# LED_aluminum.net
KiCad netlist of a schematic drawn in Altium Designer
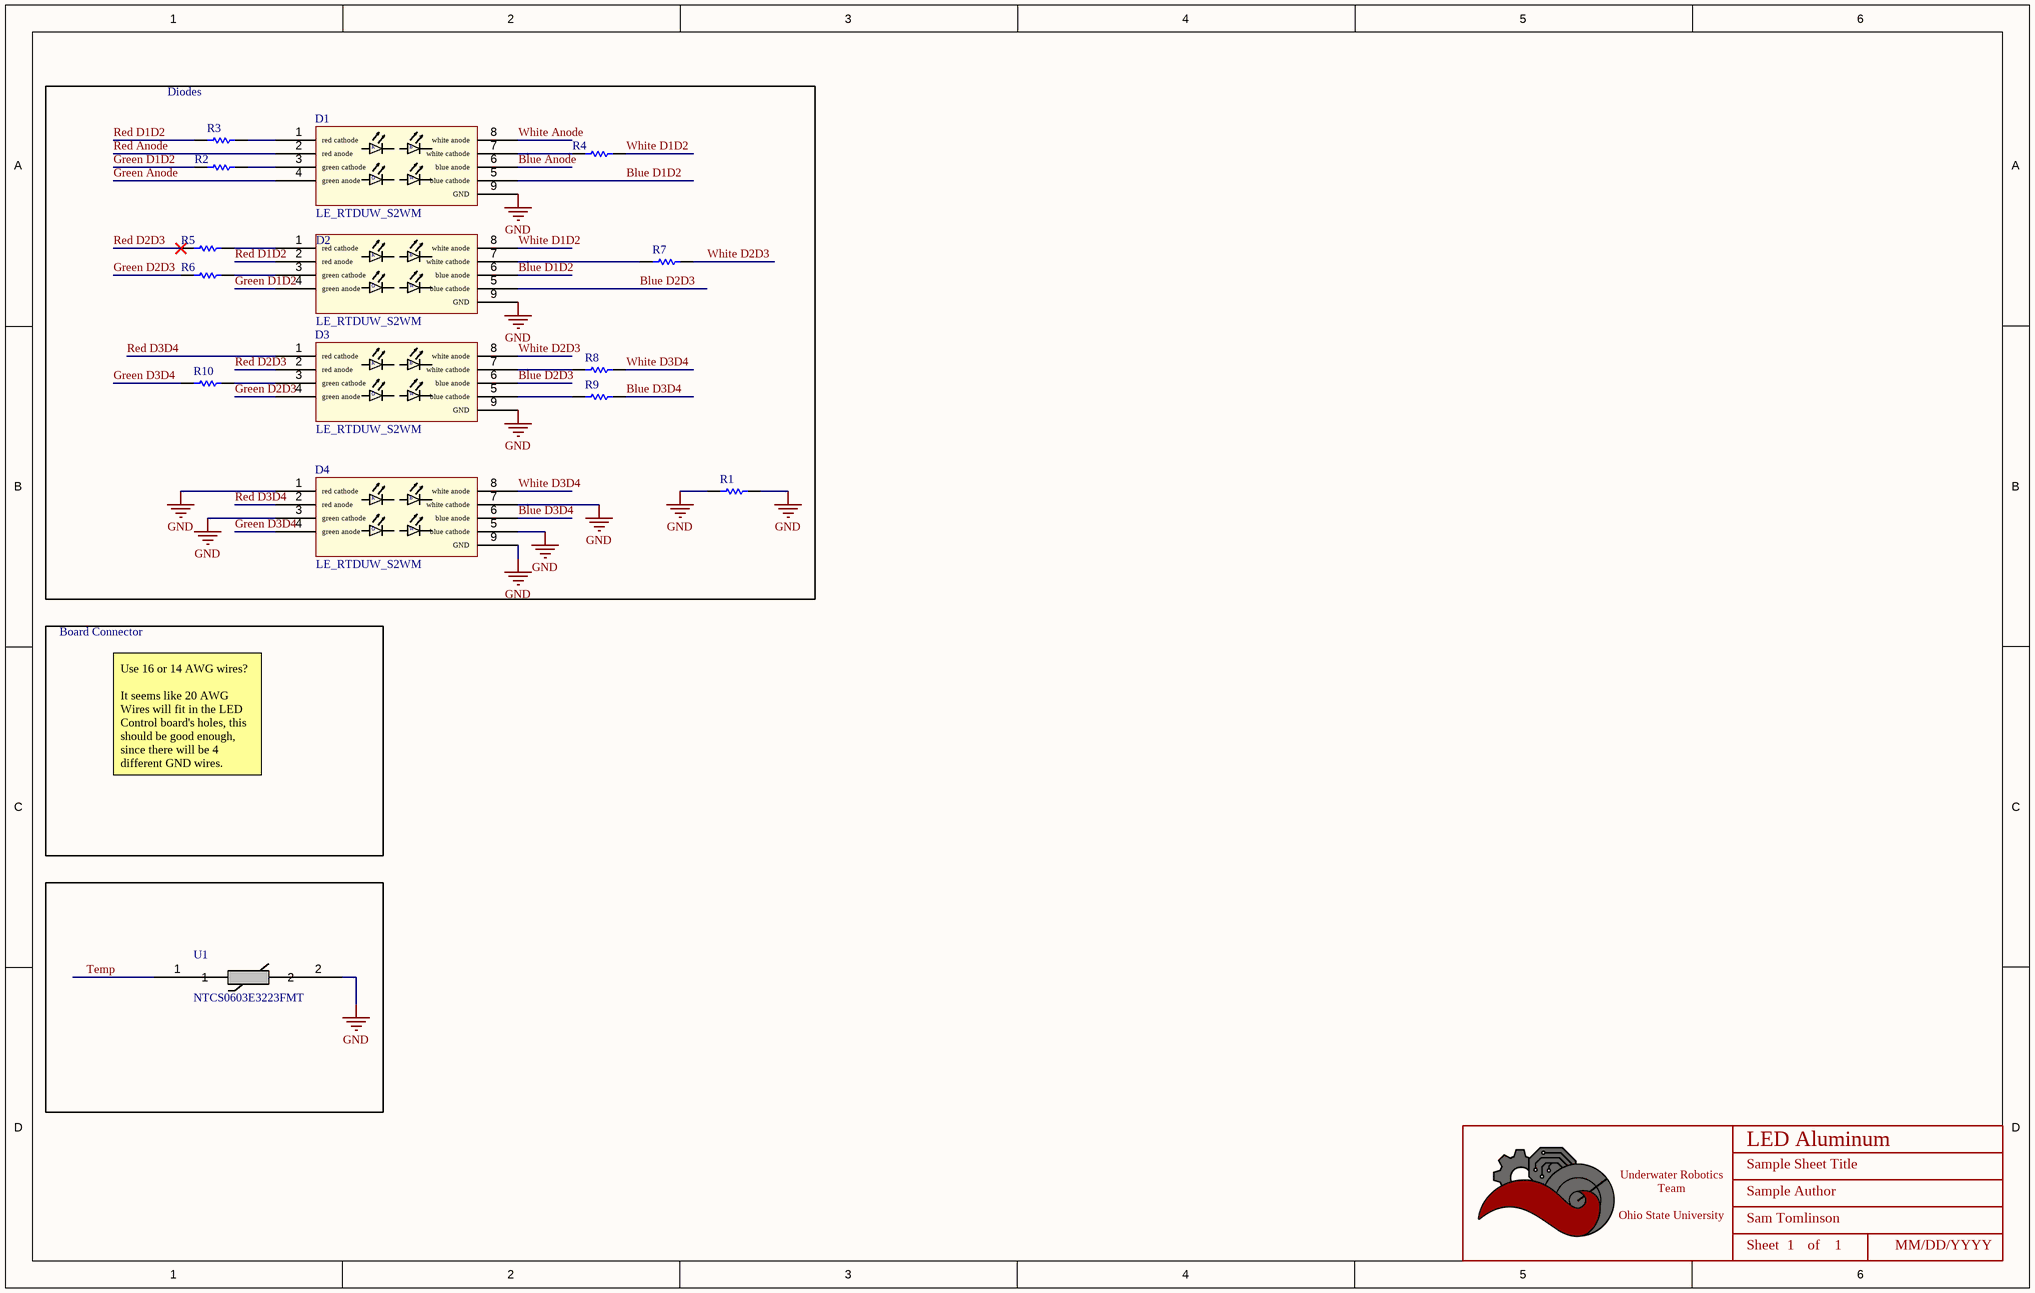
[diagram p0: LED_aluminum.SchDoc]

(export (version "E")
  (design (tool "Eeschema 10.0.6"))
  (components
    (comp (ref "*")
      (value "Title_Block")
      (footprint "LOGO")
      (description "UWRT Schematic Title Block Template\r\n\r\nCreated June 2021, Dylan Trainor")
      (libsource (lib "UWRT") (part "Title_Block"))
    )
    (comp (ref "D1")
      (value "LE_RTDUW_S2WM")
      (footprint "LE_RTDUW_S2WM")
      (description "LED OSTAR RGBW 625/527/453NM SMD")
      (libsource (lib "Diodes") (part "LE_RTDUW_S2WM"))
    )
    (comp (ref "D2")
      (value "LE_RTDUW_S2WM")
      (footprint "LE_RTDUW_S2WM")
      (description "LED OSTAR RGBW 625/527/453NM SMD")
      (libsource (lib "Diodes") (part "LE_RTDUW_S2WM"))
    )
    (comp (ref "D3")
      (value "LE_RTDUW_S2WM")
      (footprint "LE_RTDUW_S2WM")
      (description "LED OSTAR RGBW 625/527/453NM SMD")
      (libsource (lib "Diodes") (part "LE_RTDUW_S2WM"))
    )
    (comp (ref "D4")
      (value "LE_RTDUW_S2WM")
      (footprint "LE_RTDUW_S2WM")
      (description "LED OSTAR RGBW 625/527/453NM SMD")
      (libsource (lib "Diodes") (part "LE_RTDUW_S2WM"))
    )
    (comp (ref "R1")
      (value "Jumper 2512(6432)")
      (footprint "RESC2512(6432)_L")
      (description "Jumper 2512 (6432 Metric)")
      (fields (field (name "TOLERANCE") "None"))
      (libsource (lib "Altium Content Vault") (part "RES"))
    )
    (comp (ref "R2")
      (value "ERJ-8GEY0R00V")
      (footprint "RESC3216X70X50NL05T20")
      (fields (field (name "MANUFACTURER") "Panasonic"))
      (libsource (lib "Altium Content Vault") (part "RES"))
    )
    (comp (ref "R3")
      (value "Jumper 2512(6432)")
      (footprint "RESC2512(6432)_L")
      (description "Jumper 2512 (6432 Metric)")
      (fields (field (name "TOLERANCE") "None"))
      (libsource (lib "Altium Content Vault") (part "RES"))
    )
    (comp (ref "R4")
      (value "ERJ-8GEY0R00V")
      (footprint "RESC3216X70X50NL05T20")
      (fields (field (name "MANUFACTURER") "Panasonic"))
      (libsource (lib "Altium Content Vault") (part "RES"))
    )
    (comp (ref "R5")
      (value "ERJ-8GEY0R00V")
      (footprint "RESC3216X70X50NL05T20")
      (fields (field (name "MANUFACTURER") "Panasonic"))
      (libsource (lib "Altium Content Vault") (part "RES"))
    )
    (comp (ref "R6")
      (value "Jumper 2512(6432)")
      (footprint "RESC2512(6432)_L")
      (description "Jumper 2512 (6432 Metric)")
      (fields (field (name "TOLERANCE") "None"))
      (libsource (lib "Altium Content Vault") (part "RES"))
    )
    (comp (ref "R7")
      (value "ERJ-8GEY0R00V")
      (footprint "RESC3216X70X50NL05T20")
      (fields (field (name "MANUFACTURER") "Panasonic"))
      (libsource (lib "Altium Content Vault") (part "RES"))
    )
    (comp (ref "R8")
      (value "ERJ-8GEY0R00V")
      (footprint "RESC3216X70X50NL05T20")
      (fields (field (name "MANUFACTURER") "Panasonic"))
      (libsource (lib "Altium Content Vault") (part "RES"))
    )
    (comp (ref "R9")
      (value "Jumper 2512(6432)")
      (footprint "RESC2512(6432)_L")
      (description "Jumper 2512 (6432 Metric)")
      (fields (field (name "TOLERANCE") "None"))
      (libsource (lib "Altium Content Vault") (part "RES"))
    )
    (comp (ref "R10")
      (value "ERJ-8GEY0R00V")
      (footprint "RESC3216X70X50NL05T20")
      (fields (field (name "MANUFACTURER") "Panasonic"))
      (libsource (lib "Altium Content Vault") (part "RES"))
    )
    (comp (ref "U1")
      (value "NTCS0603E3223FMT")
      (footprint "NTCS0603_VIS")
      (fields (field (name "TOLERANCE") "1%"))
      (libsource (lib "Altium Content Vault") (part "NTCS0603E3223FMT"))
    )
  )
  (nets
    (net (code "1") (name "/Blue Anode") (class "Default")
      (node (ref "D1") (pin "6") (pinfunction "blue_anode_6") (pintype "passive"))
    )
    (net (code "2") (name "/Blue D1D2") (class "Default")
      (node (ref "D1") (pin "5") (pinfunction "blue_cathode_5") (pintype "passive"))
      (node (ref "D2") (pin "6") (pinfunction "blue_anode_6") (pintype "passive"))
    )
    (net (code "3") (name "/Blue D2D3") (class "Default")
      (node (ref "D2") (pin "5") (pinfunction "blue_cathode_5") (pintype "passive"))
      (node (ref "D3") (pin "6") (pinfunction "blue_anode_6") (pintype "passive"))
    )
    (net (code "4") (name "/Blue D3D4") (class "Default")
      (node (ref "D4") (pin "6") (pinfunction "blue_anode_6") (pintype "passive"))
      (node (ref "R9") (pin "2") (pinfunction "2_2") (pintype "passive"))
    )
    (net (code "5") (name "/Green Anode") (class "Default")
      (node (ref "D1") (pin "4") (pinfunction "green_anode_4") (pintype "passive"))
    )
    (net (code "6") (name "/Green D1D2") (class "Default")
      (node (ref "D2") (pin "4") (pinfunction "green_anode_4") (pintype "passive"))
      (node (ref "R2") (pin "1") (pinfunction "1_1") (pintype "passive"))
    )
    (net (code "7") (name "/Green D2D3") (class "Default")
      (node (ref "D3") (pin "4") (pinfunction "green_anode_4") (pintype "passive"))
      (node (ref "R6") (pin "1") (pinfunction "1_1") (pintype "passive"))
    )
    (net (code "8") (name "/Green D3D4") (class "Default")
      (node (ref "D4") (pin "4") (pinfunction "green_anode_4") (pintype "passive"))
      (node (ref "R10") (pin "1") (pinfunction "1_1") (pintype "passive"))
    )
    (net (code "9") (name "/Red Anode") (class "Default")
      (node (ref "D1") (pin "2") (pinfunction "red_anode_2") (pintype "passive"))
    )
    (net (code "10") (name "/Red D1D2") (class "Default")
      (node (ref "D2") (pin "2") (pinfunction "red_anode_2") (pintype "passive"))
      (node (ref "R3") (pin "1") (pinfunction "1_1") (pintype "passive"))
    )
    (net (code "11") (name "/Red D2D3") (class "Default")
      (node (ref "D3") (pin "2") (pinfunction "red_anode_2") (pintype "passive"))
      (node (ref "R5") (pin "1") (pinfunction "1_1") (pintype "passive"))
    )
    (net (code "12") (name "/Red D3D4") (class "Default")
      (node (ref "D3") (pin "1") (pinfunction "red_cathode_1") (pintype "passive"))
      (node (ref "D4") (pin "2") (pinfunction "red_anode_2") (pintype "passive"))
    )
    (net (code "13") (name "/Temp") (class "Default")
      (node (ref "U1") (pin "1") (pinfunction "1_1") (pintype "passive"))
    )
    (net (code "14") (name "/White Anode") (class "Default")
      (node (ref "D1") (pin "8") (pinfunction "white_anode_8") (pintype "passive"))
    )
    (net (code "15") (name "/White D1D2") (class "Default")
      (node (ref "D2") (pin "8") (pinfunction "white_anode_8") (pintype "passive"))
      (node (ref "R4") (pin "2") (pinfunction "2_2") (pintype "passive"))
    )
    (net (code "16") (name "/White D2D3") (class "Default")
      (node (ref "D3") (pin "8") (pinfunction "white_anode_8") (pintype "passive"))
      (node (ref "R7") (pin "2") (pinfunction "2_2") (pintype "passive"))
    )
    (net (code "17") (name "/White D3D4") (class "Default")
      (node (ref "D4") (pin "8") (pinfunction "white_anode_8") (pintype "passive"))
      (node (ref "R8") (pin "2") (pinfunction "2_2") (pintype "passive"))
    )
    (net (code "18") (name "GND") (class "Default")
      (node (ref "D1") (pin "9") (pinfunction "GND_9") (pintype "passive"))
      (node (ref "D2") (pin "9") (pinfunction "GND_9") (pintype "passive"))
      (node (ref "D3") (pin "9") (pinfunction "GND_9") (pintype "passive"))
      (node (ref "D4") (pin "1") (pinfunction "red_cathode_1") (pintype "passive"))
      (node (ref "D4") (pin "3") (pinfunction "green_cathode_3") (pintype "passive"))
      (node (ref "D4") (pin "5") (pinfunction "blue_cathode_5") (pintype "passive"))
      (node (ref "D4") (pin "7") (pinfunction "white_cathode_7") (pintype "passive"))
      (node (ref "D4") (pin "9") (pinfunction "GND_9") (pintype "passive"))
      (node (ref "R1") (pin "1") (pinfunction "1_1") (pintype "passive"))
      (node (ref "R1") (pin "2") (pinfunction "2_2") (pintype "passive"))
      (node (ref "U1") (pin "2") (pinfunction "2_2") (pintype "passive"))
    )
    (net (code "19") (name "Net-(D1-green_cathode)") (class "Default")
      (node (ref "D1") (pin "3") (pinfunction "green_cathode_3") (pintype "passive"))
      (node (ref "R2") (pin "2") (pinfunction "2_2") (pintype "passive"))
    )
    (net (code "20") (name "Net-(D1-red_cathode)") (class "Default")
      (node (ref "D1") (pin "1") (pinfunction "red_cathode_1") (pintype "passive"))
      (node (ref "R3") (pin "2") (pinfunction "2_2") (pintype "passive"))
    )
    (net (code "21") (name "Net-(D1-white_cathode)") (class "Default")
      (node (ref "D1") (pin "7") (pinfunction "white_cathode_7") (pintype "passive"))
      (node (ref "R4") (pin "1") (pinfunction "1_1") (pintype "passive"))
    )
    (net (code "22") (name "Net-(D2-green_cathode)") (class "Default")
      (node (ref "D2") (pin "3") (pinfunction "green_cathode_3") (pintype "passive"))
      (node (ref "R6") (pin "2") (pinfunction "2_2") (pintype "passive"))
    )
    (net (code "23") (name "Net-(D2-red_cathode)") (class "Default")
      (node (ref "D2") (pin "1") (pinfunction "red_cathode_1") (pintype "passive"))
      (node (ref "R5") (pin "2") (pinfunction "2_2") (pintype "passive"))
    )
    (net (code "24") (name "Net-(D2-white_cathode)") (class "Default")
      (node (ref "D2") (pin "7") (pinfunction "white_cathode_7") (pintype "passive"))
      (node (ref "R7") (pin "1") (pinfunction "1_1") (pintype "passive"))
    )
    (net (code "25") (name "Net-(D3-blue_cathode)") (class "Default")
      (node (ref "D3") (pin "5") (pinfunction "blue_cathode_5") (pintype "passive"))
      (node (ref "R9") (pin "1") (pinfunction "1_1") (pintype "passive"))
    )
    (net (code "26") (name "Net-(D3-green_cathode)") (class "Default")
      (node (ref "D3") (pin "3") (pinfunction "green_cathode_3") (pintype "passive"))
      (node (ref "R10") (pin "2") (pinfunction "2_2") (pintype "passive"))
    )
    (net (code "27") (name "Net-(D3-white_cathode)") (class "Default")
      (node (ref "D3") (pin "7") (pinfunction "white_cathode_7") (pintype "passive"))
      (node (ref "R8") (pin "1") (pinfunction "1_1") (pintype "passive"))
    )
  )
)
